# C128_Keyb_Test.net
KiCad netlist of a schematic drawn in EAGLE
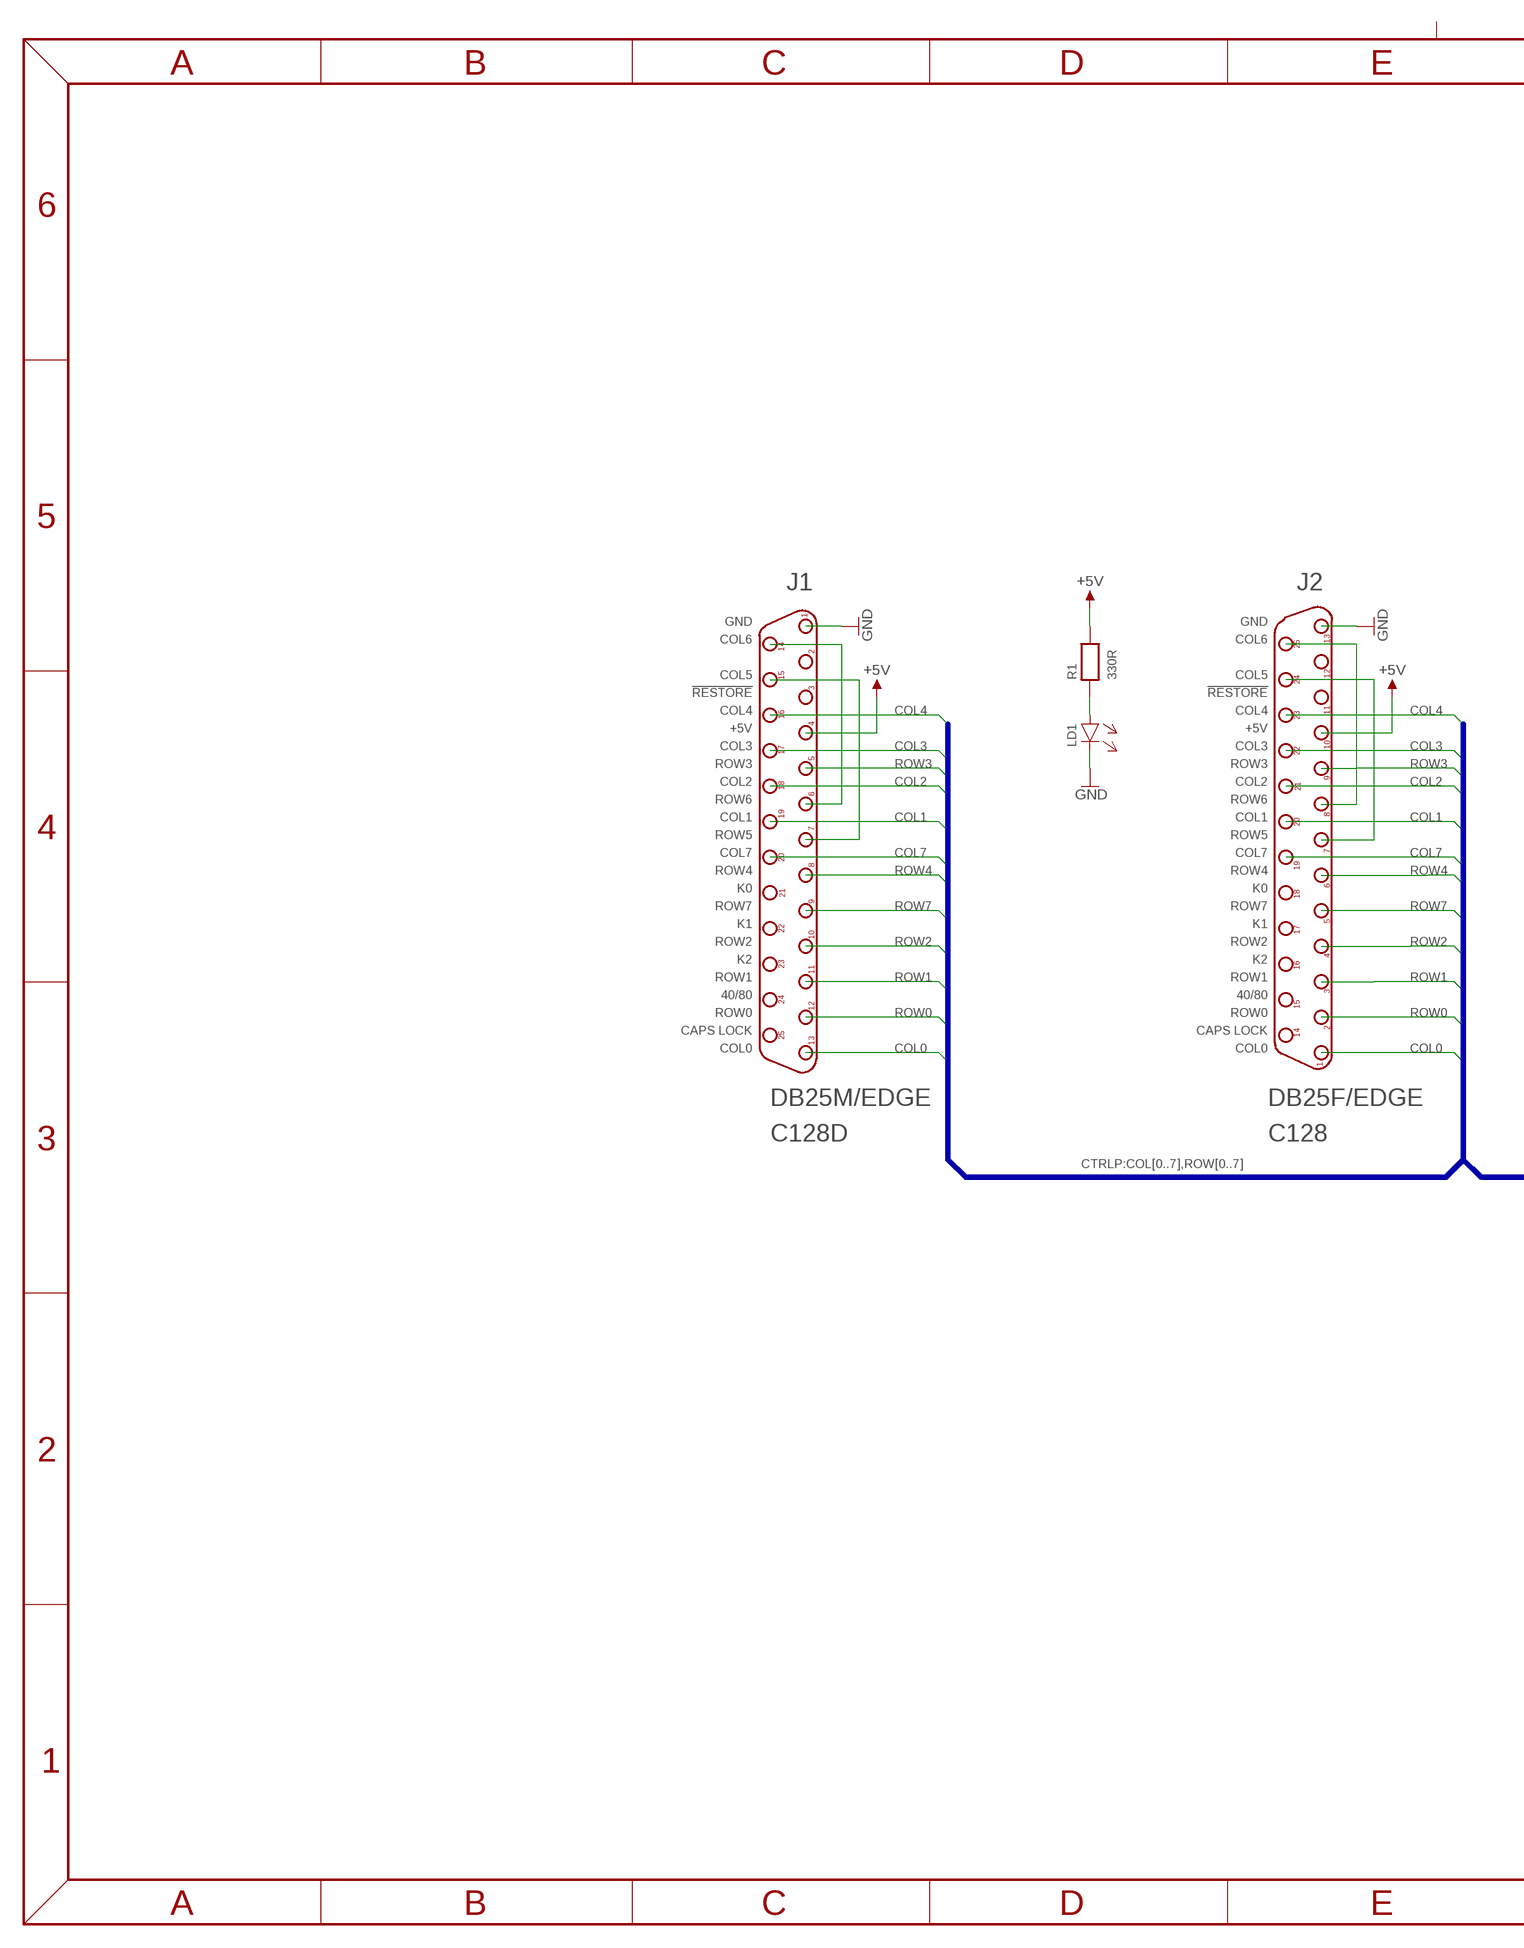
[diagram p0: schematic, sheet 1, part 1 of 2]
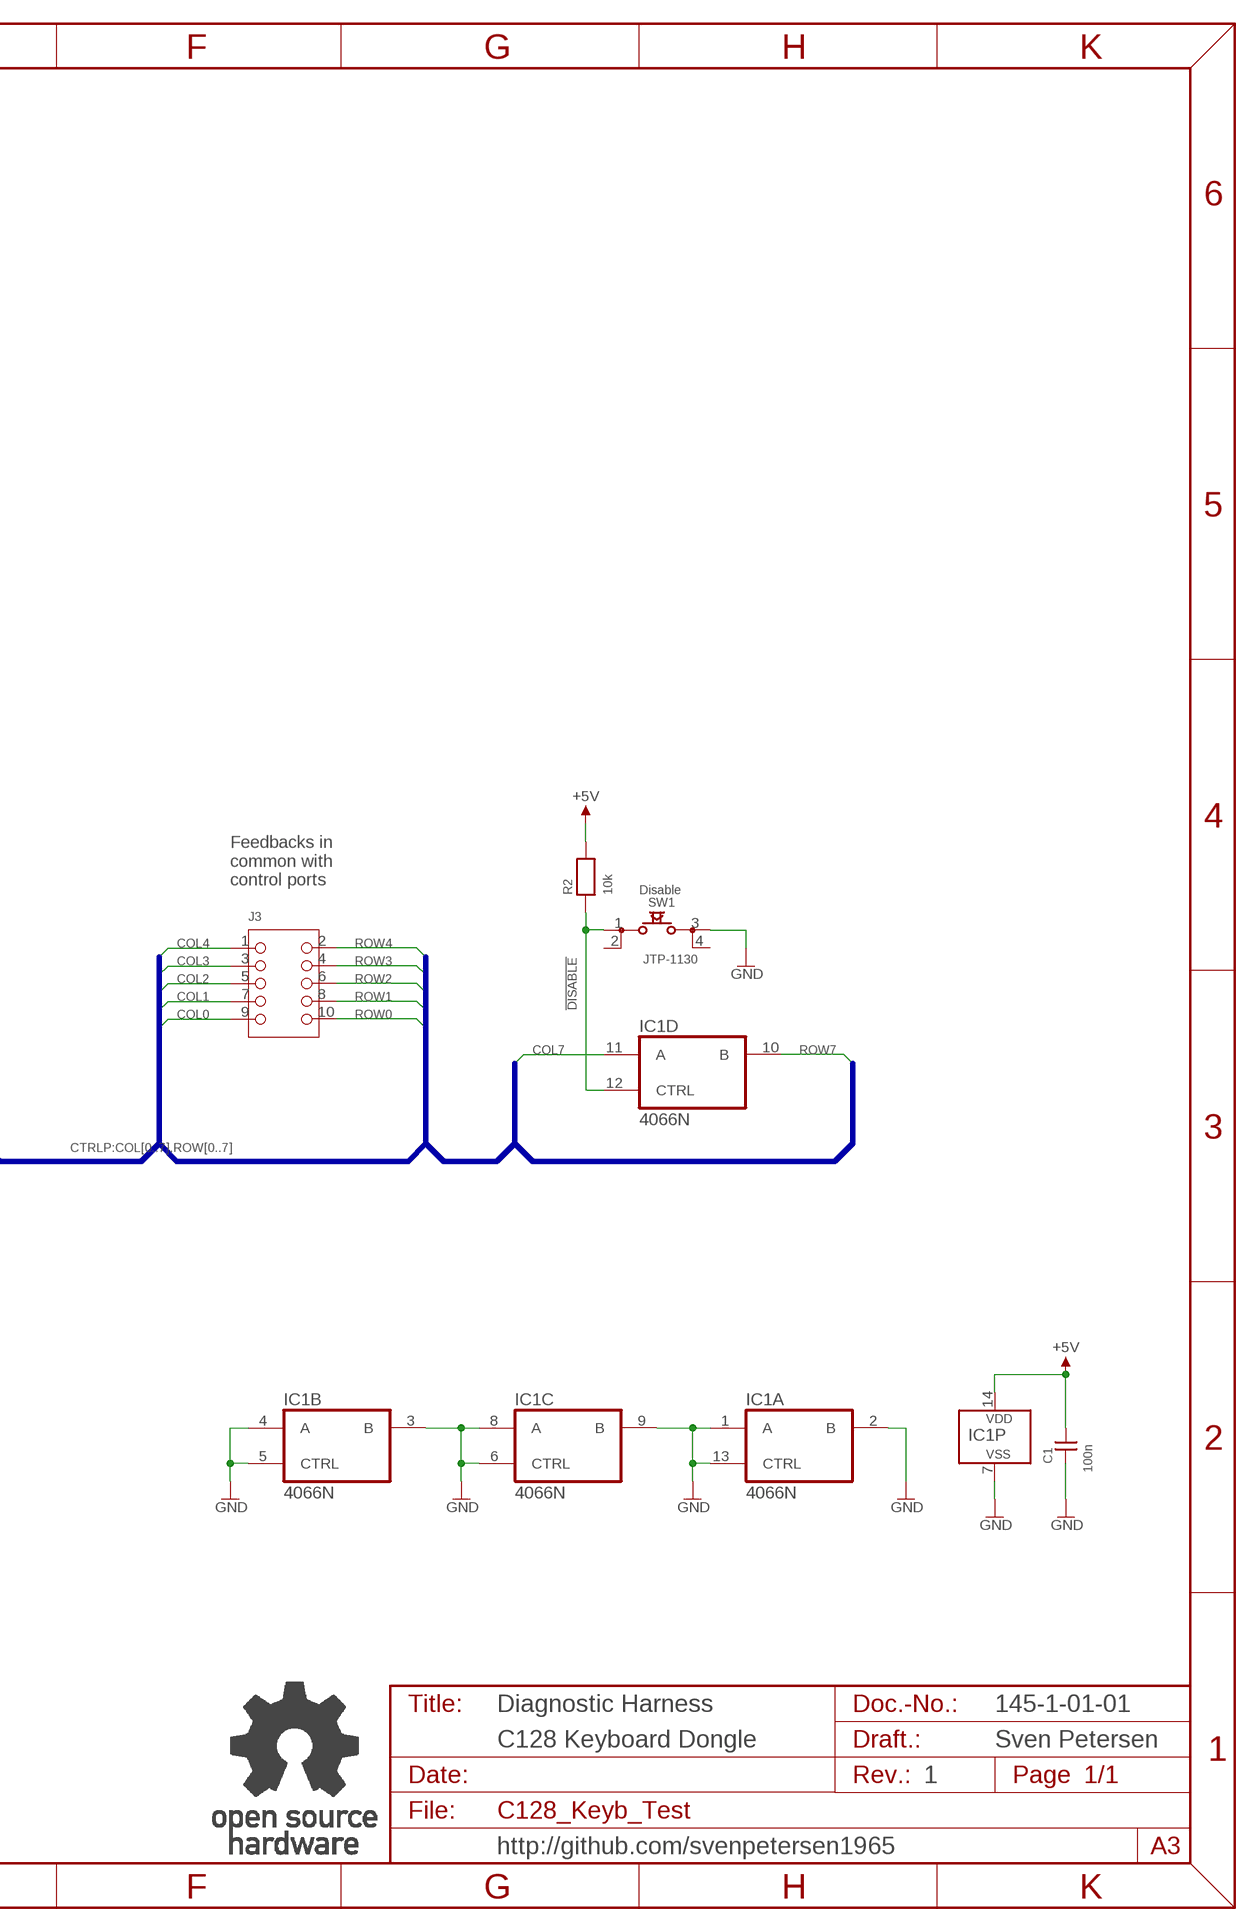
[diagram p1: schematic, sheet 1, part 2 of 2]

(export (version "E")
  (design (tool "Eeschema 10.0.6"))
  (components
    (comp (ref "C1")
      (value "100n")
      (footprint "eagle-import:C-2,5")
      (libsource (lib "eagle-import") (part "CAP01"))
    )
    (comp (ref "IC1")
      (value "4066N")
      (footprint "eagle-import:DIL14")
      (libsource (lib "eagle-import") (part "4066N"))
    )
    (comp (ref "J1")
      (value "DB25M/EDGE")
      (footprint "eagle-import:DB25M-EDGE")
      (libsource (lib "eagle-import") (part "DB25M/EDGE"))
    )
    (comp (ref "J2")
      (value "DB25F/EDGE")
      (footprint "eagle-import:DB25F-EDGE")
      (libsource (lib "eagle-import") (part "DB25F/EDGE"))
    )
    (comp (ref "J3")
      (value "2X05WV")
      (footprint "eagle-import:2X05WV")
      (libsource (lib "eagle-import") (part "2X05WV"))
    )
    (comp (ref "LD1")
      (value "3MM")
      (footprint "eagle-import:3MM")
      (libsource (lib "eagle-import") (part "3MM"))
    )
    (comp (ref "R1")
      (value "330R")
      (footprint "eagle-import:R-10")
      (libsource (lib "eagle-import") (part "RES04"))
    )
    (comp (ref "R2")
      (value "10k")
      (footprint "eagle-import:R-10")
      (libsource (lib "eagle-import") (part "RES04"))
    )
    (comp (ref "SW1")
      (value "JTP-1130")
      (footprint "eagle-import:JTP-1130")
      (libsource (lib "eagle-import") (part "JTP-1130"))
    )
    (comp (ref "U$20")
      (value "OPEN_SOURCE_HW")
      (footprint "eagle-import:OPENHW")
      (libsource (lib "eagle-import") (part "OPEN_SOURCE_HW"))
    )
  )
  (nets
    (net (code "1") (name "+5V") (class "Default")
      (node (ref "C1") (pin "2") (pinfunction "2_2") (pintype "passive"))
      (node (ref "IC1") (pin "14") (pinfunction "VDD_14") (pintype "power_in"))
      (node (ref "J1") (pin "4") (pinfunction "4_4") (pintype "passive"))
      (node (ref "J2") (pin "10") (pinfunction "10_10") (pintype "passive"))
      (node (ref "R1") (pin "2") (pinfunction "2_2") (pintype "passive"))
      (node (ref "R2") (pin "2") (pinfunction "2_2") (pintype "passive"))
    )
    (net (code "2") (name "/COL0") (class "Default")
      (node (ref "J1") (pin "13") (pinfunction "13_13") (pintype "passive"))
      (node (ref "J2") (pin "1") (pinfunction "1_1") (pintype "passive"))
      (node (ref "J3") (pin "9") (pinfunction "9_9") (pintype "passive"))
    )
    (net (code "3") (name "/COL1") (class "Default")
      (node (ref "J1") (pin "19") (pinfunction "19_19") (pintype "passive"))
      (node (ref "J2") (pin "20") (pinfunction "20_20") (pintype "passive"))
      (node (ref "J3") (pin "7") (pinfunction "7_7") (pintype "passive"))
    )
    (net (code "4") (name "/COL2") (class "Default")
      (node (ref "J1") (pin "18") (pinfunction "18_18") (pintype "passive"))
      (node (ref "J2") (pin "21") (pinfunction "21_21") (pintype "passive"))
      (node (ref "J3") (pin "5") (pinfunction "5_5") (pintype "passive"))
    )
    (net (code "5") (name "/COL3") (class "Default")
      (node (ref "J1") (pin "17") (pinfunction "17_17") (pintype "passive"))
      (node (ref "J2") (pin "22") (pinfunction "22_22") (pintype "passive"))
      (node (ref "J3") (pin "3") (pinfunction "3_3") (pintype "passive"))
    )
    (net (code "6") (name "/COL4") (class "Default")
      (node (ref "J1") (pin "16") (pinfunction "16_16") (pintype "passive"))
      (node (ref "J2") (pin "23") (pinfunction "23_23") (pintype "passive"))
      (node (ref "J3") (pin "1") (pinfunction "1_1") (pintype "passive"))
    )
    (net (code "7") (name "/COL7") (class "Default")
      (node (ref "IC1") (pin "11") (pinfunction "A_11") (pintype "tri_state"))
      (node (ref "J1") (pin "20") (pinfunction "20_20") (pintype "passive"))
      (node (ref "J2") (pin "19") (pinfunction "19_19") (pintype "passive"))
    )
    (net (code "8") (name "/ROW0") (class "Default")
      (node (ref "J1") (pin "12") (pinfunction "12_12") (pintype "passive"))
      (node (ref "J2") (pin "2") (pinfunction "2_2") (pintype "passive"))
      (node (ref "J3") (pin "10") (pinfunction "10_10") (pintype "passive"))
    )
    (net (code "9") (name "/ROW1") (class "Default")
      (node (ref "J1") (pin "11") (pinfunction "11_11") (pintype "passive"))
      (node (ref "J2") (pin "3") (pinfunction "3_3") (pintype "passive"))
      (node (ref "J3") (pin "8") (pinfunction "8_8") (pintype "passive"))
    )
    (net (code "10") (name "/ROW2") (class "Default")
      (node (ref "J1") (pin "10") (pinfunction "10_10") (pintype "passive"))
      (node (ref "J2") (pin "4") (pinfunction "4_4") (pintype "passive"))
      (node (ref "J3") (pin "6") (pinfunction "6_6") (pintype "passive"))
    )
    (net (code "11") (name "/ROW3") (class "Default")
      (node (ref "J1") (pin "5") (pinfunction "5_5") (pintype "passive"))
      (node (ref "J2") (pin "9") (pinfunction "9_9") (pintype "passive"))
      (node (ref "J3") (pin "4") (pinfunction "4_4") (pintype "passive"))
    )
    (net (code "12") (name "/ROW4") (class "Default")
      (node (ref "J1") (pin "8") (pinfunction "8_8") (pintype "passive"))
      (node (ref "J2") (pin "6") (pinfunction "6_6") (pintype "passive"))
      (node (ref "J3") (pin "2") (pinfunction "2_2") (pintype "passive"))
    )
    (net (code "13") (name "/ROW7") (class "Default")
      (node (ref "IC1") (pin "10") (pinfunction "B_10") (pintype "tri_state"))
      (node (ref "J1") (pin "9") (pinfunction "9_9") (pintype "passive"))
      (node (ref "J2") (pin "5") (pinfunction "5_5") (pintype "passive"))
    )
    (net (code "15") (name "/~{DISABLE}") (class "Default")
      (node (ref "IC1") (pin "12") (pinfunction "CTRL_12") (pintype "input"))
      (node (ref "R2") (pin "1") (pinfunction "1_1") (pintype "passive"))
      (node (ref "SW1") (pin "1") (pinfunction "1_1") (pintype "passive"))
    )
    (net (code "16") (name "GND") (class "Default")
      (node (ref "C1") (pin "1") (pinfunction "1_1") (pintype "passive"))
      (node (ref "IC1") (pin "1") (pinfunction "A_1") (pintype "tri_state"))
      (node (ref "IC1") (pin "13") (pinfunction "CTRL_13") (pintype "input"))
      (node (ref "IC1") (pin "2") (pinfunction "B_2") (pintype "tri_state"))
      (node (ref "IC1") (pin "3") (pinfunction "B_3") (pintype "tri_state"))
      (node (ref "IC1") (pin "4") (pinfunction "A_4") (pintype "tri_state"))
      (node (ref "IC1") (pin "5") (pinfunction "CTRL_5") (pintype "input"))
      (node (ref "IC1") (pin "6") (pinfunction "CTRL_6") (pintype "input"))
      (node (ref "IC1") (pin "7") (pinfunction "VSS_7") (pintype "power_in"))
      (node (ref "IC1") (pin "8") (pinfunction "A_8") (pintype "tri_state"))
      (node (ref "IC1") (pin "9") (pinfunction "B_9") (pintype "tri_state"))
      (node (ref "J1") (pin "1") (pinfunction "1_1") (pintype "passive"))
      (node (ref "J2") (pin "13") (pinfunction "13_13") (pintype "passive"))
      (node (ref "LD1") (pin "C") (pinfunction "K_C") (pintype "bidirectional"))
      (node (ref "SW1") (pin "3") (pinfunction "3_3") (pintype "passive"))
    )
    (net (code "17") (name "Net-(J1-Pad14)") (class "Default")
      (node (ref "J1") (pin "14") (pinfunction "14_14") (pintype "passive"))
      (node (ref "J1") (pin "6") (pinfunction "6_6") (pintype "passive"))
    )
    (net (code "18") (name "Net-(J1-Pad15)") (class "Default")
      (node (ref "J1") (pin "15") (pinfunction "15_15") (pintype "passive"))
      (node (ref "J1") (pin "7") (pinfunction "7_7") (pintype "passive"))
    )
    (net (code "19") (name "Net-(J2-Pad24)") (class "Default")
      (node (ref "J2") (pin "24") (pinfunction "24_24") (pintype "passive"))
      (node (ref "J2") (pin "7") (pinfunction "7_7") (pintype "passive"))
    )
    (net (code "20") (name "Net-(J2-Pad25)") (class "Default")
      (node (ref "J2") (pin "25") (pinfunction "25_25") (pintype "passive"))
      (node (ref "J2") (pin "8") (pinfunction "8_8") (pintype "passive"))
    )
    (net (code "21") (name "Net-(LD1-PadA)") (class "Default")
      (node (ref "LD1") (pin "A") (pinfunction "A_A") (pintype "bidirectional"))
      (node (ref "R1") (pin "1") (pinfunction "1_1") (pintype "passive"))
    )
    (net (code "22") (name "unconnected-(J1-Pad2)") (class "Default")
      (node (ref "J1") (pin "2") (pinfunction "2_2") (pintype "passive"))
    )
    (net (code "23") (name "unconnected-(J1-Pad3)") (class "Default")
      (node (ref "J1") (pin "3") (pinfunction "3_3") (pintype "passive"))
    )
    (net (code "24") (name "unconnected-(J1-Pad21)") (class "Default")
      (node (ref "J1") (pin "21") (pinfunction "21_21") (pintype "passive"))
    )
    (net (code "25") (name "unconnected-(J1-Pad22)") (class "Default")
      (node (ref "J1") (pin "22") (pinfunction "22_22") (pintype "passive"))
    )
    (net (code "26") (name "unconnected-(J1-Pad23)") (class "Default")
      (node (ref "J1") (pin "23") (pinfunction "23_23") (pintype "passive"))
    )
    (net (code "27") (name "unconnected-(J1-Pad24)") (class "Default")
      (node (ref "J1") (pin "24") (pinfunction "24_24") (pintype "passive"))
    )
    (net (code "28") (name "unconnected-(J1-Pad25)") (class "Default")
      (node (ref "J1") (pin "25") (pinfunction "25_25") (pintype "passive"))
    )
    (net (code "29") (name "unconnected-(J2-Pad11)") (class "Default")
      (node (ref "J2") (pin "11") (pinfunction "11_11") (pintype "passive"))
    )
    (net (code "30") (name "unconnected-(J2-Pad12)") (class "Default")
      (node (ref "J2") (pin "12") (pinfunction "12_12") (pintype "passive"))
    )
    (net (code "31") (name "unconnected-(J2-Pad14)") (class "Default")
      (node (ref "J2") (pin "14") (pinfunction "14_14") (pintype "passive"))
    )
    (net (code "32") (name "unconnected-(J2-Pad15)") (class "Default")
      (node (ref "J2") (pin "15") (pinfunction "15_15") (pintype "passive"))
    )
    (net (code "33") (name "unconnected-(J2-Pad16)") (class "Default")
      (node (ref "J2") (pin "16") (pinfunction "16_16") (pintype "passive"))
    )
    (net (code "34") (name "unconnected-(J2-Pad17)") (class "Default")
      (node (ref "J2") (pin "17") (pinfunction "17_17") (pintype "passive"))
    )
    (net (code "35") (name "unconnected-(J2-Pad18)") (class "Default")
      (node (ref "J2") (pin "18") (pinfunction "18_18") (pintype "passive"))
    )
    (net (code "36") (name "unconnected-(SW1-Pad2)") (class "Default")
      (node (ref "SW1") (pin "2") (pinfunction "2_2") (pintype "passive"))
    )
    (net (code "37") (name "unconnected-(SW1-Pad4)") (class "Default")
      (node (ref "SW1") (pin "4") (pinfunction "4_4") (pintype "passive"))
    )
  )
)
